# sensors.net
KiCad netlist of a schematic drawn in EAGLE
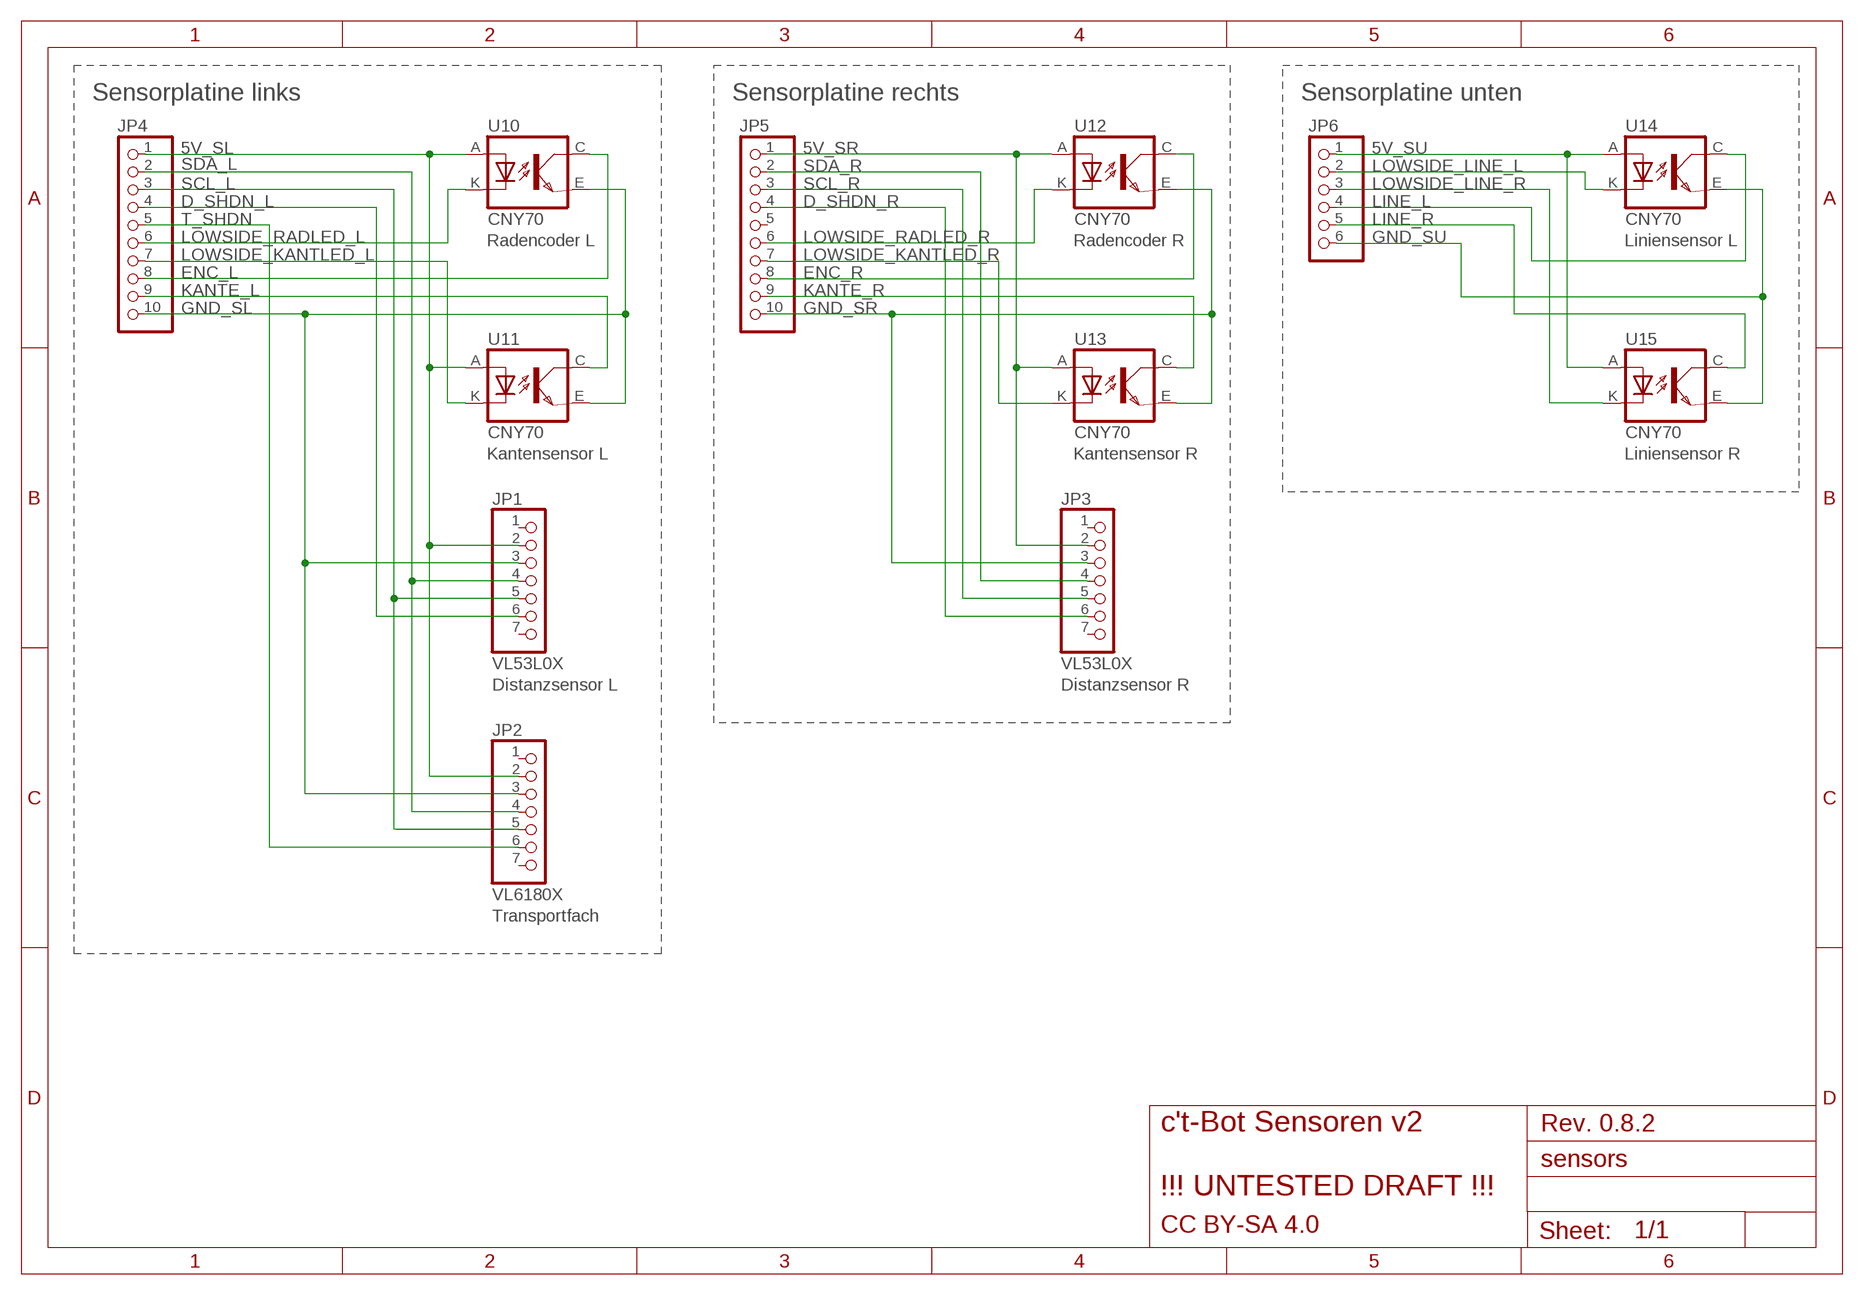
[diagram p0: schematic, sheet 1]

(export (version "E")
  (design (tool "Eeschema 10.0.6"))
  (components
    (comp (ref "JP1")
      (value "VL53L0X")
      (footprint "eagle-import:1X07")
      (libsource (lib "eagle-import") (part "PINHD-1X7"))
    )
    (comp (ref "JP2")
      (value "VL6180X")
      (footprint "eagle-import:1X07")
      (libsource (lib "eagle-import") (part "PINHD-1X7"))
    )
    (comp (ref "JP3")
      (value "VL53L0X")
      (footprint "eagle-import:1X07")
      (libsource (lib "eagle-import") (part "PINHD-1X7"))
    )
    (comp (ref "JP4")
      (value "PINHD-1X10")
      (footprint "eagle-import:1X10")
      (libsource (lib "eagle-import") (part "PINHD-1X10"))
    )
    (comp (ref "JP5")
      (value "PINHD-1X10")
      (footprint "eagle-import:1X10")
      (libsource (lib "eagle-import") (part "PINHD-1X10"))
    )
    (comp (ref "JP6")
      (value "PINHD-1X6")
      (footprint "eagle-import:1X06")
      (libsource (lib "eagle-import") (part "PINHD-1X6"))
    )
    (comp (ref "U10")
      (value "CNY70")
      (footprint "eagle-import:4")
      (libsource (lib "eagle-import") (part "CNY70"))
    )
    (comp (ref "U11")
      (value "CNY70")
      (footprint "eagle-import:4")
      (libsource (lib "eagle-import") (part "CNY70"))
    )
    (comp (ref "U12")
      (value "CNY70")
      (footprint "eagle-import:4")
      (libsource (lib "eagle-import") (part "CNY70"))
    )
    (comp (ref "U13")
      (value "CNY70")
      (footprint "eagle-import:4")
      (libsource (lib "eagle-import") (part "CNY70"))
    )
    (comp (ref "U14")
      (value "CNY70")
      (footprint "eagle-import:4")
      (libsource (lib "eagle-import") (part "CNY70"))
    )
    (comp (ref "U15")
      (value "CNY70")
      (footprint "eagle-import:4")
      (libsource (lib "eagle-import") (part "CNY70"))
    )
  )
  (nets
    (net (code "1") (name "/5V_SL") (class "Default")
      (node (ref "JP1") (pin "2") (pinfunction "2_2") (pintype "passive"))
      (node (ref "JP2") (pin "2") (pinfunction "2_2") (pintype "passive"))
      (node (ref "JP4") (pin "1") (pinfunction "1_1") (pintype "passive"))
      (node (ref "U10") (pin "A") (pinfunction "A_A") (pintype "passive"))
      (node (ref "U11") (pin "A") (pinfunction "A_A") (pintype "passive"))
    )
    (net (code "2") (name "/5V_SR") (class "Default")
      (node (ref "JP3") (pin "2") (pinfunction "2_2") (pintype "passive"))
      (node (ref "JP5") (pin "1") (pinfunction "1_1") (pintype "passive"))
      (node (ref "U12") (pin "A") (pinfunction "A_A") (pintype "passive"))
      (node (ref "U13") (pin "A") (pinfunction "A_A") (pintype "passive"))
    )
    (net (code "3") (name "/5V_SU") (class "Default")
      (node (ref "JP6") (pin "1") (pinfunction "1_1") (pintype "passive"))
      (node (ref "U14") (pin "A") (pinfunction "A_A") (pintype "passive"))
      (node (ref "U15") (pin "A") (pinfunction "A_A") (pintype "passive"))
    )
    (net (code "4") (name "/D_SHDN_L") (class "Default")
      (node (ref "JP1") (pin "6") (pinfunction "6_6") (pintype "passive"))
      (node (ref "JP4") (pin "4") (pinfunction "4_4") (pintype "passive"))
    )
    (net (code "5") (name "/D_SHDN_R") (class "Default")
      (node (ref "JP3") (pin "6") (pinfunction "6_6") (pintype "passive"))
      (node (ref "JP5") (pin "4") (pinfunction "4_4") (pintype "passive"))
    )
    (net (code "6") (name "/ENC_L") (class "Default")
      (node (ref "JP4") (pin "8") (pinfunction "8_8") (pintype "passive"))
      (node (ref "U10") (pin "C") (pinfunction "COL_C") (pintype "passive"))
    )
    (net (code "7") (name "/ENC_R") (class "Default")
      (node (ref "JP5") (pin "8") (pinfunction "8_8") (pintype "passive"))
      (node (ref "U12") (pin "C") (pinfunction "COL_C") (pintype "passive"))
    )
    (net (code "8") (name "/GND_SL") (class "Default")
      (node (ref "JP1") (pin "3") (pinfunction "3_3") (pintype "passive"))
      (node (ref "JP2") (pin "3") (pinfunction "3_3") (pintype "passive"))
      (node (ref "JP4") (pin "10") (pinfunction "10_10") (pintype "passive"))
      (node (ref "U10") (pin "E") (pinfunction "EMI_E") (pintype "passive"))
      (node (ref "U11") (pin "E") (pinfunction "EMI_E") (pintype "passive"))
    )
    (net (code "9") (name "/GND_SR") (class "Default")
      (node (ref "JP3") (pin "3") (pinfunction "3_3") (pintype "passive"))
      (node (ref "JP5") (pin "10") (pinfunction "10_10") (pintype "passive"))
      (node (ref "U12") (pin "E") (pinfunction "EMI_E") (pintype "passive"))
      (node (ref "U13") (pin "E") (pinfunction "EMI_E") (pintype "passive"))
    )
    (net (code "10") (name "/GND_SU") (class "Default")
      (node (ref "JP6") (pin "6") (pinfunction "6_6") (pintype "passive"))
      (node (ref "U14") (pin "E") (pinfunction "EMI_E") (pintype "passive"))
      (node (ref "U15") (pin "E") (pinfunction "EMI_E") (pintype "passive"))
    )
    (net (code "11") (name "/KANTE_L") (class "Default")
      (node (ref "JP4") (pin "9") (pinfunction "9_9") (pintype "passive"))
      (node (ref "U11") (pin "C") (pinfunction "COL_C") (pintype "passive"))
    )
    (net (code "12") (name "/KANTE_R") (class "Default")
      (node (ref "JP5") (pin "9") (pinfunction "9_9") (pintype "passive"))
      (node (ref "U13") (pin "C") (pinfunction "COL_C") (pintype "passive"))
    )
    (net (code "13") (name "/LINE_L") (class "Default")
      (node (ref "JP6") (pin "4") (pinfunction "4_4") (pintype "passive"))
      (node (ref "U14") (pin "C") (pinfunction "COL_C") (pintype "passive"))
    )
    (net (code "14") (name "/LINE_R") (class "Default")
      (node (ref "JP6") (pin "5") (pinfunction "5_5") (pintype "passive"))
      (node (ref "U15") (pin "C") (pinfunction "COL_C") (pintype "passive"))
    )
    (net (code "15") (name "/LOWSIDE_KANTLED_L") (class "Default")
      (node (ref "JP4") (pin "7") (pinfunction "7_7") (pintype "passive"))
      (node (ref "U11") (pin "K") (pinfunction "C_K") (pintype "passive"))
    )
    (net (code "16") (name "/LOWSIDE_KANTLED_R") (class "Default")
      (node (ref "JP5") (pin "7") (pinfunction "7_7") (pintype "passive"))
      (node (ref "U13") (pin "K") (pinfunction "C_K") (pintype "passive"))
    )
    (net (code "17") (name "/LOWSIDE_LINE_L") (class "Default")
      (node (ref "JP6") (pin "2") (pinfunction "2_2") (pintype "passive"))
      (node (ref "U14") (pin "K") (pinfunction "C_K") (pintype "passive"))
    )
    (net (code "18") (name "/LOWSIDE_LINE_R") (class "Default")
      (node (ref "JP6") (pin "3") (pinfunction "3_3") (pintype "passive"))
      (node (ref "U15") (pin "K") (pinfunction "C_K") (pintype "passive"))
    )
    (net (code "19") (name "/LOWSIDE_RADLED_L") (class "Default")
      (node (ref "JP4") (pin "6") (pinfunction "6_6") (pintype "passive"))
      (node (ref "U10") (pin "K") (pinfunction "C_K") (pintype "passive"))
    )
    (net (code "20") (name "/LOWSIDE_RADLED_R") (class "Default")
      (node (ref "JP5") (pin "6") (pinfunction "6_6") (pintype "passive"))
      (node (ref "U12") (pin "K") (pinfunction "C_K") (pintype "passive"))
    )
    (net (code "21") (name "/SCL_L") (class "Default")
      (node (ref "JP1") (pin "5") (pinfunction "5_5") (pintype "passive"))
      (node (ref "JP2") (pin "5") (pinfunction "5_5") (pintype "passive"))
      (node (ref "JP4") (pin "3") (pinfunction "3_3") (pintype "passive"))
    )
    (net (code "22") (name "/SCL_R") (class "Default")
      (node (ref "JP3") (pin "5") (pinfunction "5_5") (pintype "passive"))
      (node (ref "JP5") (pin "3") (pinfunction "3_3") (pintype "passive"))
    )
    (net (code "23") (name "/SDA_L") (class "Default")
      (node (ref "JP1") (pin "4") (pinfunction "4_4") (pintype "passive"))
      (node (ref "JP2") (pin "4") (pinfunction "4_4") (pintype "passive"))
      (node (ref "JP4") (pin "2") (pinfunction "2_2") (pintype "passive"))
    )
    (net (code "24") (name "/SDA_R") (class "Default")
      (node (ref "JP3") (pin "4") (pinfunction "4_4") (pintype "passive"))
      (node (ref "JP5") (pin "2") (pinfunction "2_2") (pintype "passive"))
    )
    (net (code "25") (name "/T_SHDN") (class "Default")
      (node (ref "JP2") (pin "6") (pinfunction "6_6") (pintype "passive"))
      (node (ref "JP4") (pin "5") (pinfunction "5_5") (pintype "passive"))
    )
    (net (code "26") (name "unconnected-(JP1-Pad1)") (class "Default")
      (node (ref "JP1") (pin "1") (pinfunction "1_1") (pintype "passive"))
    )
    (net (code "27") (name "unconnected-(JP1-Pad7)") (class "Default")
      (node (ref "JP1") (pin "7") (pinfunction "7_7") (pintype "passive"))
    )
    (net (code "28") (name "unconnected-(JP2-Pad1)") (class "Default")
      (node (ref "JP2") (pin "1") (pinfunction "1_1") (pintype "passive"))
    )
    (net (code "29") (name "unconnected-(JP2-Pad7)") (class "Default")
      (node (ref "JP2") (pin "7") (pinfunction "7_7") (pintype "passive"))
    )
    (net (code "30") (name "unconnected-(JP3-Pad1)") (class "Default")
      (node (ref "JP3") (pin "1") (pinfunction "1_1") (pintype "passive"))
    )
    (net (code "31") (name "unconnected-(JP3-Pad7)") (class "Default")
      (node (ref "JP3") (pin "7") (pinfunction "7_7") (pintype "passive"))
    )
    (net (code "32") (name "unconnected-(JP5-Pad5)") (class "Default")
      (node (ref "JP5") (pin "5") (pinfunction "5_5") (pintype "passive"))
    )
  )
)
